# ProDoc_Board1_2_2024-09-12_1.net
KiCad netlist of a schematic drawn in EasyEDA Pro
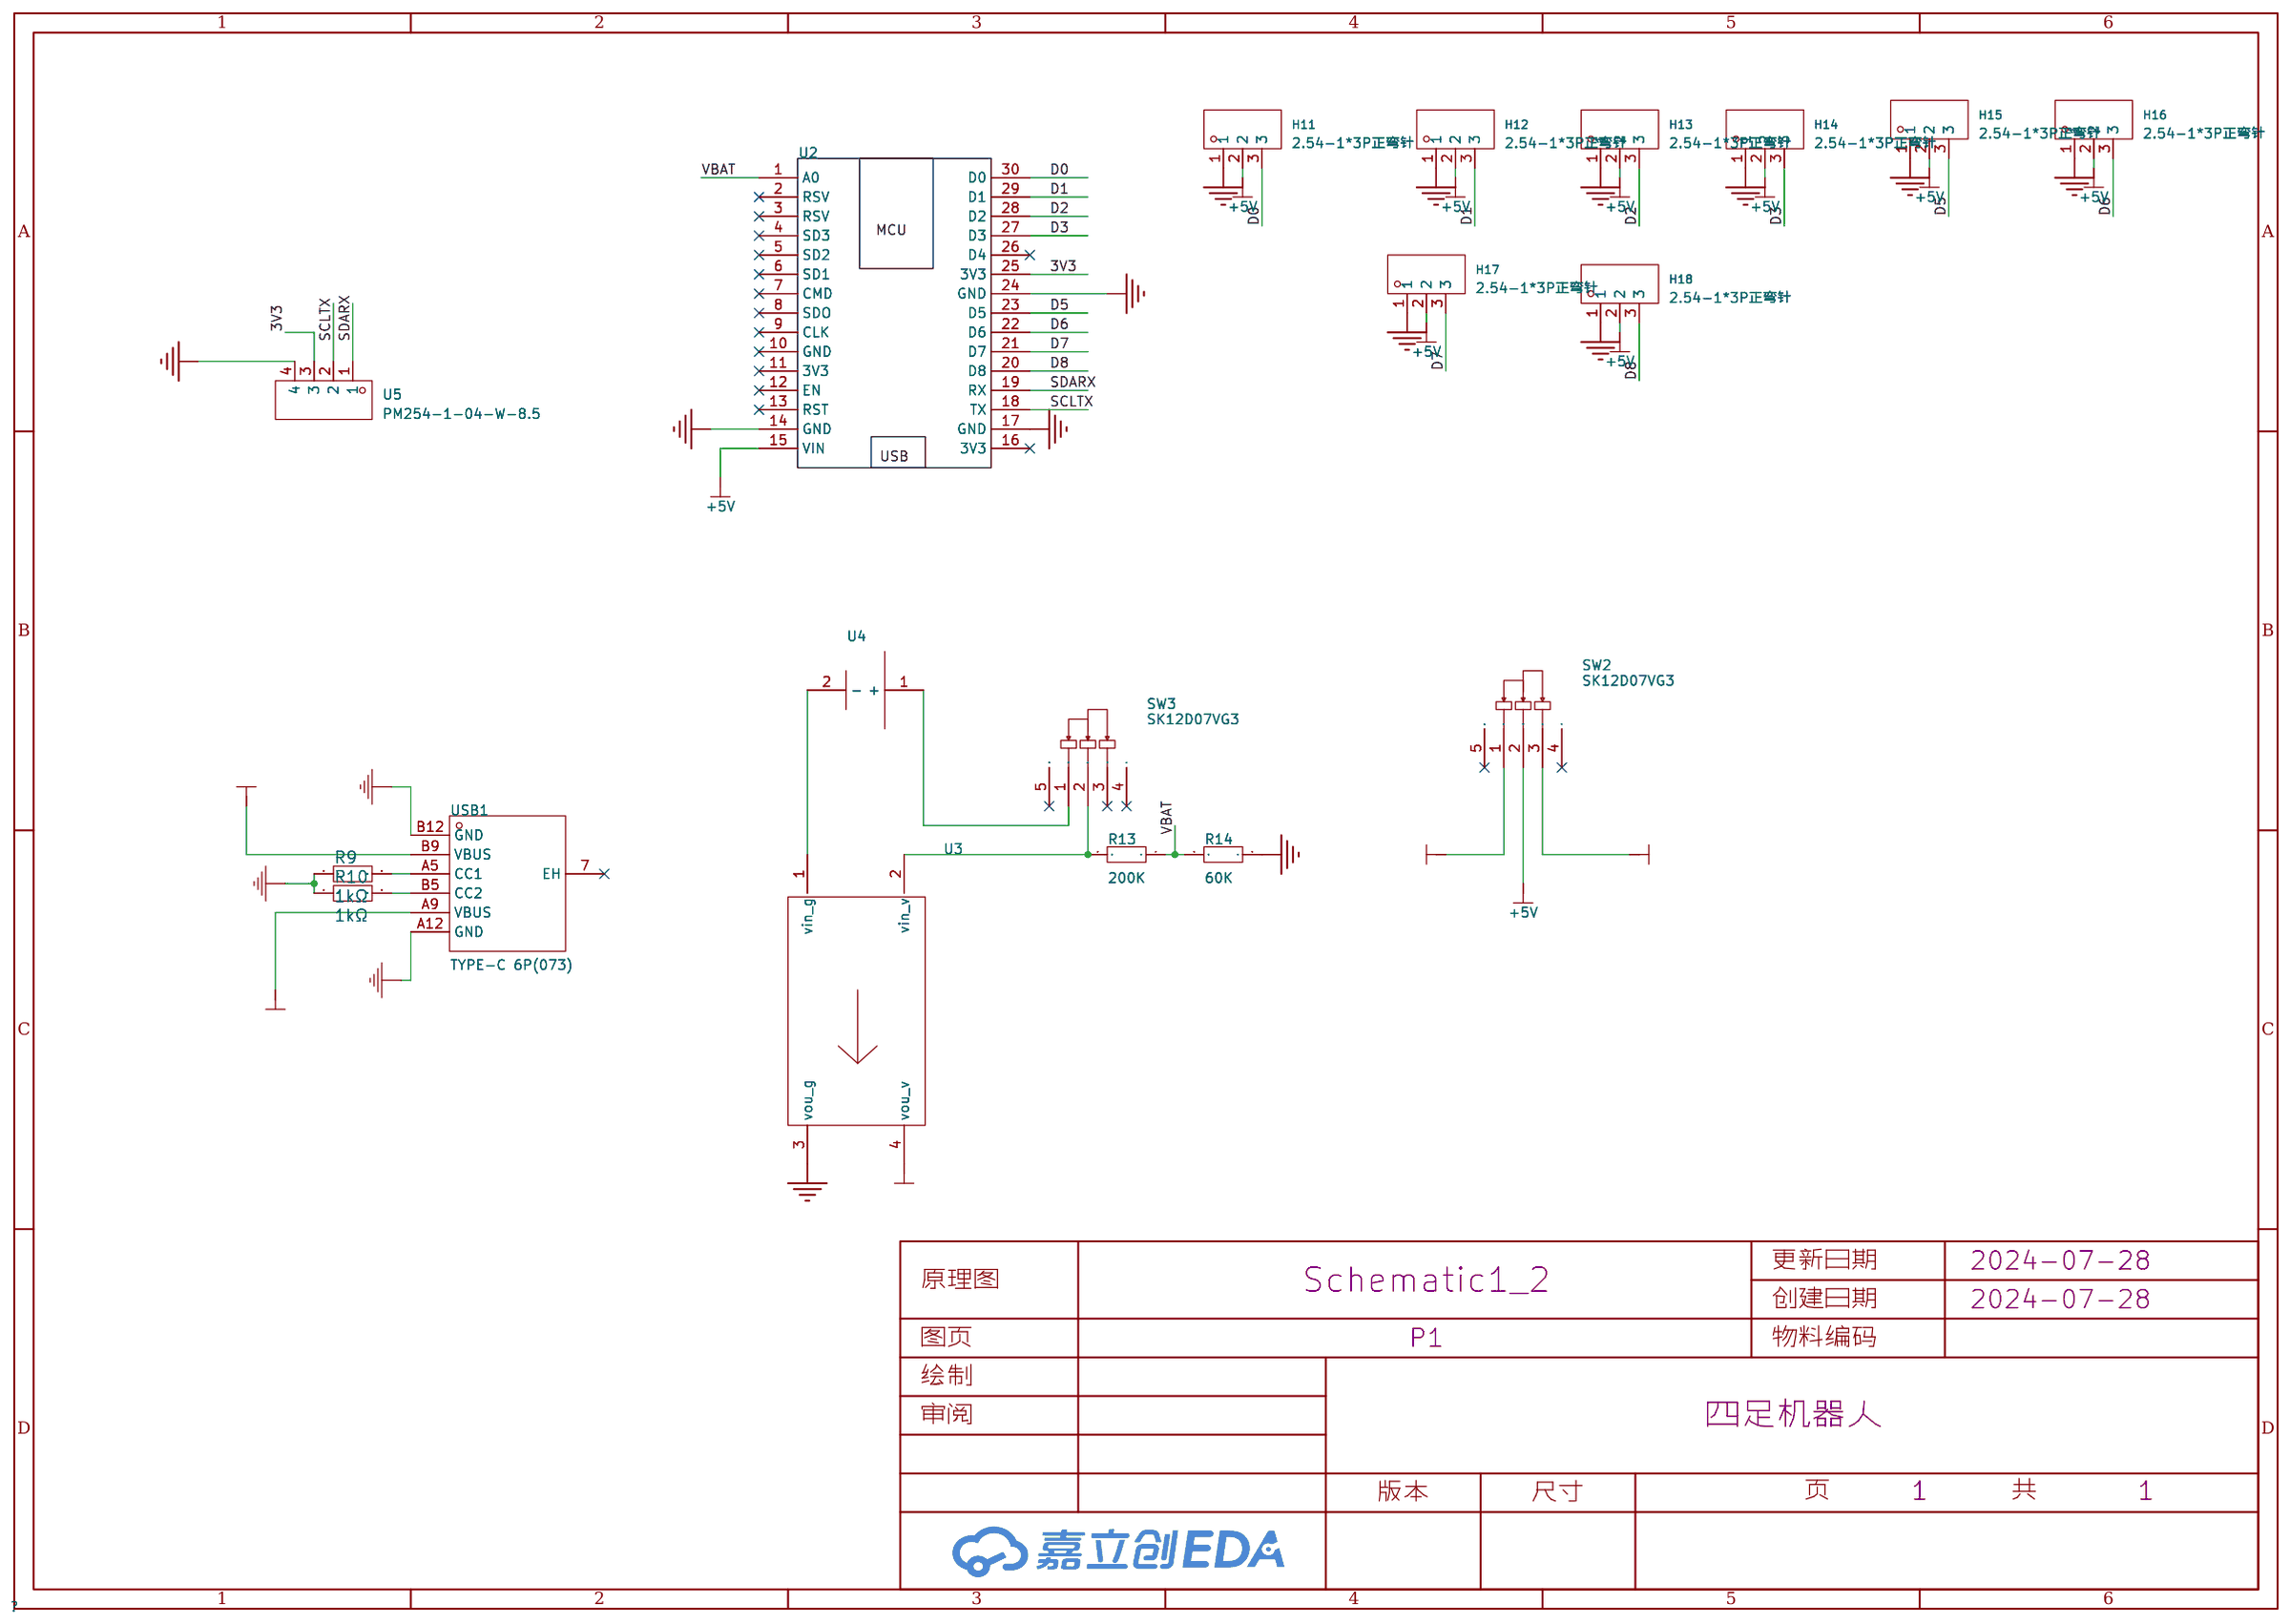
[diagram p0: schematic sheet]

(export (version "E")
  (design (tool "Eeschema 10.0.6"))
  (components
    (comp (ref "H11")
      (value "2.54-1*3P正弯针")
      (footprint "easyedapro:HDR-TH_3P-P2.54-H-M-BW7.2-P")
      (fields (field (name "Manufacturer") "BOOMELE(博穆精密)"))
      (libsource (lib "easyedapro") (part "C92159"))
    )
    (comp (ref "H12")
      (value "2.54-1*3P正弯针")
      (footprint "easyedapro:HDR-TH_3P-P2.54-H-M-BW7.2-P")
      (fields (field (name "Manufacturer") "BOOMELE(博穆精密)"))
      (libsource (lib "easyedapro") (part "C92159"))
    )
    (comp (ref "H13")
      (value "2.54-1*3P正弯针")
      (footprint "easyedapro:HDR-TH_3P-P2.54-H-M-BW7.2-P")
      (fields (field (name "Manufacturer") "BOOMELE(博穆精密)"))
      (libsource (lib "easyedapro") (part "C92159"))
    )
    (comp (ref "H14")
      (value "2.54-1*3P正弯针")
      (footprint "easyedapro:HDR-TH_3P-P2.54-H-M-BW7.2-P")
      (fields (field (name "Manufacturer") "BOOMELE(博穆精密)"))
      (libsource (lib "easyedapro") (part "C92159"))
    )
    (comp (ref "H15")
      (value "2.54-1*3P正弯针")
      (footprint "easyedapro:HDR-TH_3P-P2.54-H-M-BW7.2-P")
      (fields (field (name "Manufacturer") "BOOMELE(博穆精密)"))
      (libsource (lib "easyedapro") (part "C92159"))
    )
    (comp (ref "H16")
      (value "2.54-1*3P正弯针")
      (footprint "easyedapro:HDR-TH_3P-P2.54-H-M-BW7.2-P")
      (fields (field (name "Manufacturer") "BOOMELE(博穆精密)"))
      (libsource (lib "easyedapro") (part "C92159"))
    )
    (comp (ref "H17")
      (value "2.54-1*3P正弯针")
      (footprint "easyedapro:HDR-TH_3P-P2.54-H-M-BW7.2-P")
      (fields (field (name "Manufacturer") "BOOMELE(博穆精密)"))
      (libsource (lib "easyedapro") (part "C92159"))
    )
    (comp (ref "H18")
      (value "2.54-1*3P正弯针")
      (footprint "easyedapro:HDR-TH_3P-P2.54-H-M-BW7.2-P")
      (fields (field (name "Manufacturer") "BOOMELE(博穆精密)"))
      (libsource (lib "easyedapro") (part "C92159"))
    )
    (comp (ref "R9") (value "1kΩ") (libsource (lib "easyedapro") (part "1.5k")))
    (comp (ref "R10") (value "1kΩ") (libsource (lib "easyedapro") (part "1.5k")))
    (comp (ref "R13")
      (value "200K")
      (fields
        (field (name "Manufacturer Part") "0603WAF1002T5E")
        (field (name "Manufacturer") "UNI-ROYAL(厚声)")
      )
      (libsource (lib "easyedapro") (part "电阻"))
    )
    (comp (ref "R14")
      (value "60K")
      (fields
        (field (name "Manufacturer Part") "0603WAF1002T5E")
        (field (name "Manufacturer") "UNI-ROYAL(厚声)")
      )
      (libsource (lib "easyedapro") (part "电阻"))
    )
    (comp (ref "SW2")
      (value "SK12D07VG3")
      (footprint "easyedapro:SW-TH_SK12D07VG3")
      (description "电路结构:单刀双掷;安装方式:侧插;开关颜色:-;额定电流(DC):500mA;额定电压(DC):50V;额定电流(AC):-;额定电压(AC):-;机械寿命:5千次;")
      (fields (field (name "Manufacturer") "SHOU HAN(首韩)"))
      (libsource (lib "easyedapro") (part "SK12D07VG3_C431547"))
    )
    (comp (ref "SW3")
      (value "SK12D07VG3")
      (footprint "easyedapro:SW-TH_SK12D07VG3")
      (description "电路结构:单刀双掷;安装方式:侧插;开关颜色:-;额定电流(DC):500mA;额定电压(DC):50V;额定电流(AC):-;额定电压(AC):-;机械寿命:5千次;")
      (fields (field (name "Manufacturer") "SHOU HAN(首韩)"))
      (libsource (lib "easyedapro") (part "SK12D07VG3_C431547"))
    )
    (comp (ref "U2") (value "~") (libsource (lib "easyedapro") (part "nodemcu")))
    (comp (ref "U3") (value "~") (libsource (lib "easyedapro") (part "5v5a降压模块")))
    (comp (ref "U4") (value "~") (libsource (lib "easyedapro") (part "7.4电池输入口")))
    (comp (ref "U5")
      (value "PM254-1-04-W-8.5")
      (footprint "easyedapro:HDR-TH_4P-P2.54-H-F-W10.0-N")
      (fields (field (name "Manufacturer") "HCTL(华灿天禄)"))
      (libsource (lib "easyedapro") (part "PM254-1-04-W-8.5"))
    )
    (comp (ref "USB1")
      (value "TYPE-C 6P(073)")
      (footprint "easyedapro:TYPE-C-SMD_TYPE-C-6P")
      (description "连接器类型:Type-C;标准:-;公母:母;端口数量:1;触点数量:6P;安装方式:卧贴;额定电流 - 电源:5A;工作温度范围:-25°C~+85°C;")
      (fields (field (name "Manufacturer") "SHOU HAN(首韩)"))
      (libsource (lib "easyedapro") (part "TYPE-C 6P(073)"))
    )
  )
  (nets
    (net (code "1") (name "+5V") (class "Default")
      (node (ref "H11") (pin "2") (pinfunction "2_2") (pintype "input"))
      (node (ref "H12") (pin "2") (pinfunction "2_2") (pintype "input"))
      (node (ref "H13") (pin "2") (pinfunction "2_2") (pintype "input"))
      (node (ref "H14") (pin "2") (pinfunction "2_2") (pintype "input"))
      (node (ref "H15") (pin "2") (pinfunction "2_2") (pintype "input"))
      (node (ref "H16") (pin "2") (pinfunction "2_2") (pintype "input"))
      (node (ref "H17") (pin "2") (pinfunction "2_2") (pintype "input"))
      (node (ref "H18") (pin "2") (pinfunction "2_2") (pintype "input"))
      (node (ref "SW2") (pin "2") (pinfunction "2_2") (pintype "unspecified"))
      (node (ref "U2") (pin "15") (pinfunction "VIN_15") (pintype "input"))
    )
    (net (code "2") (name "/3V3") (class "Default")
      (node (ref "U2") (pin "25") (pinfunction "3V3_25") (pintype "input"))
      (node (ref "U5") (pin "3") (pinfunction "3_3") (pintype "unspecified"))
    )
    (net (code "3") (name "/D0") (class "Default")
      (node (ref "H11") (pin "3") (pinfunction "3_3") (pintype "input"))
      (node (ref "U2") (pin "30") (pinfunction "D0_30") (pintype "input"))
    )
    (net (code "4") (name "/D1") (class "Default")
      (node (ref "H12") (pin "3") (pinfunction "3_3") (pintype "input"))
      (node (ref "U2") (pin "29") (pinfunction "D1_29") (pintype "input"))
    )
    (net (code "5") (name "/D2") (class "Default")
      (node (ref "H13") (pin "3") (pinfunction "3_3") (pintype "input"))
      (node (ref "U2") (pin "28") (pinfunction "D2_28") (pintype "input"))
    )
    (net (code "6") (name "/D3") (class "Default")
      (node (ref "H14") (pin "3") (pinfunction "3_3") (pintype "input"))
      (node (ref "U2") (pin "27") (pinfunction "D3_27") (pintype "input"))
    )
    (net (code "7") (name "/D5") (class "Default")
      (node (ref "H15") (pin "3") (pinfunction "3_3") (pintype "input"))
      (node (ref "U2") (pin "23") (pinfunction "D5_23") (pintype "input"))
    )
    (net (code "8") (name "/D6") (class "Default")
      (node (ref "H16") (pin "3") (pinfunction "3_3") (pintype "input"))
      (node (ref "U2") (pin "22") (pinfunction "D6_22") (pintype "input"))
    )
    (net (code "9") (name "/D7") (class "Default")
      (node (ref "H17") (pin "3") (pinfunction "3_3") (pintype "input"))
      (node (ref "U2") (pin "21") (pinfunction "D7_21") (pintype "input"))
    )
    (net (code "10") (name "/D8") (class "Default")
      (node (ref "H18") (pin "3") (pinfunction "3_3") (pintype "input"))
      (node (ref "U2") (pin "20") (pinfunction "D8_20") (pintype "input"))
    )
    (net (code "11") (name "/SCLTX") (class "Default")
      (node (ref "U2") (pin "18") (pinfunction "TX_18") (pintype "input"))
      (node (ref "U5") (pin "2") (pinfunction "2_2") (pintype "unspecified"))
    )
    (net (code "12") (name "/SDARX") (class "Default")
      (node (ref "U2") (pin "19") (pinfunction "RX_19") (pintype "input"))
      (node (ref "U5") (pin "1") (pinfunction "1_1") (pintype "unspecified"))
    )
    (net (code "13") (name "/VBAT") (class "Default")
      (node (ref "R13") (pin "1") (pinfunction "1_1") (pintype "input"))
      (node (ref "R14") (pin "2") (pinfunction "2_2") (pintype "input"))
      (node (ref "U2") (pin "1") (pinfunction "A0_1") (pintype "input"))
    )
    (net (code "14") (name "GND") (class "Default")
      (node (ref "H11") (pin "1") (pinfunction "1_1") (pintype "input"))
      (node (ref "H12") (pin "1") (pinfunction "1_1") (pintype "input"))
      (node (ref "H13") (pin "1") (pinfunction "1_1") (pintype "input"))
      (node (ref "H14") (pin "1") (pinfunction "1_1") (pintype "input"))
      (node (ref "H15") (pin "1") (pinfunction "1_1") (pintype "input"))
      (node (ref "H16") (pin "1") (pinfunction "1_1") (pintype "input"))
      (node (ref "H17") (pin "1") (pinfunction "1_1") (pintype "input"))
      (node (ref "H18") (pin "1") (pinfunction "1_1") (pintype "input"))
      (node (ref "R10") (pin "1") (pinfunction "1_1") (pintype "input"))
      (node (ref "R14") (pin "1") (pinfunction "1_1") (pintype "input"))
      (node (ref "R9") (pin "1") (pinfunction "1_1") (pintype "input"))
      (node (ref "U2") (pin "14") (pinfunction "GND_14") (pintype "input"))
      (node (ref "U2") (pin "17") (pinfunction "GND_17") (pintype "input"))
      (node (ref "U2") (pin "24") (pinfunction "GND_24") (pintype "input"))
      (node (ref "U3") (pin "3") (pinfunction "vou_g_3") (pintype "input"))
      (node (ref "U5") (pin "4") (pinfunction "4_4") (pintype "unspecified"))
      (node (ref "USB1") (pin "A12") (pinfunction "GND_A12") (pintype "unspecified"))
      (node (ref "USB1") (pin "B12") (pinfunction "GND_B12") (pintype "unspecified"))
    )
    (net (code "15") (name "Net-(U3-vin_g)") (class "Default")
      (node (ref "U3") (pin "1") (pinfunction "vin_g_1") (pintype "input"))
      (node (ref "U4") (pin "2") (pinfunction "-_2") (pintype "input"))
    )
    (net (code "16") (name "Net-(U3-vin_v)") (class "Default")
      (node (ref "R13") (pin "2") (pinfunction "2_2") (pintype "input"))
      (node (ref "SW3") (pin "2") (pinfunction "2_2") (pintype "unspecified"))
      (node (ref "U3") (pin "2") (pinfunction "vin_v_2") (pintype "input"))
    )
    (net (code "17") (name "Net-(U4-+)") (class "Default")
      (node (ref "SW3") (pin "1") (pinfunction "1_1") (pintype "unspecified"))
      (node (ref "U4") (pin "1") (pinfunction "+_1") (pintype "input"))
    )
    (net (code "18") (name "Net-(USB1-CC1)") (class "Default")
      (node (ref "R9") (pin "2") (pinfunction "2_2") (pintype "input"))
      (node (ref "USB1") (pin "A5") (pinfunction "CC1_A5") (pintype "unspecified"))
    )
    (net (code "19") (name "Net-(USB1-CC2)") (class "Default")
      (node (ref "R10") (pin "2") (pinfunction "2_2") (pintype "input"))
      (node (ref "USB1") (pin "B5") (pinfunction "CC2_B5") (pintype "unspecified"))
    )
    (net (code "20") (name "USB5V") (class "Default")
      (node (ref "SW2") (pin "1") (pinfunction "1_1") (pintype "unspecified"))
      (node (ref "USB1") (pin "A9") (pinfunction "VBUS_A9") (pintype "unspecified"))
      (node (ref "USB1") (pin "B9") (pinfunction "VBUS_B9") (pintype "unspecified"))
    )
    (net (code "21") (name "VBUCK5V") (class "Default")
      (node (ref "SW2") (pin "3") (pinfunction "3_3") (pintype "unspecified"))
      (node (ref "U3") (pin "4") (pinfunction "vou_v_4") (pintype "input"))
    )
    (net (code "22") (name "unconnected-(SW2-Pad4)") (class "Default")
      (node (ref "SW2") (pin "4") (pinfunction "4_4") (pintype "unspecified+no_connect"))
    )
    (net (code "23") (name "unconnected-(SW2-Pad5)") (class "Default")
      (node (ref "SW2") (pin "5") (pinfunction "5_5") (pintype "unspecified+no_connect"))
    )
    (net (code "24") (name "unconnected-(SW3-Pad3)") (class "Default")
      (node (ref "SW3") (pin "3") (pinfunction "3_3") (pintype "unspecified+no_connect"))
    )
    (net (code "25") (name "unconnected-(SW3-Pad4)") (class "Default")
      (node (ref "SW3") (pin "4") (pinfunction "4_4") (pintype "unspecified+no_connect"))
    )
    (net (code "26") (name "unconnected-(SW3-Pad5)") (class "Default")
      (node (ref "SW3") (pin "5") (pinfunction "5_5") (pintype "unspecified+no_connect"))
    )
    (net (code "27") (name "unconnected-(U2-3V3-Pad11)") (class "Default")
      (node (ref "U2") (pin "11") (pinfunction "3V3_11") (pintype "input+no_connect"))
    )
    (net (code "28") (name "unconnected-(U2-3V3-Pad16)") (class "Default")
      (node (ref "U2") (pin "16") (pinfunction "3V3_16") (pintype "input+no_connect"))
    )
    (net (code "29") (name "unconnected-(U2-CLK-Pad9)") (class "Default")
      (node (ref "U2") (pin "9") (pinfunction "CLK_9") (pintype "input+no_connect"))
    )
    (net (code "30") (name "unconnected-(U2-CMD-Pad7)") (class "Default")
      (node (ref "U2") (pin "7") (pinfunction "CMD_7") (pintype "input+no_connect"))
    )
    (net (code "31") (name "unconnected-(U2-D4-Pad26)") (class "Default")
      (node (ref "U2") (pin "26") (pinfunction "D4_26") (pintype "input+no_connect"))
    )
    (net (code "32") (name "unconnected-(U2-EN-Pad12)") (class "Default")
      (node (ref "U2") (pin "12") (pinfunction "EN_12") (pintype "input+no_connect"))
    )
    (net (code "33") (name "unconnected-(U2-GND-Pad10)") (class "Default")
      (node (ref "U2") (pin "10") (pinfunction "GND_10") (pintype "input+no_connect"))
    )
    (net (code "34") (name "unconnected-(U2-RST-Pad13)") (class "Default")
      (node (ref "U2") (pin "13") (pinfunction "RST_13") (pintype "input+no_connect"))
    )
    (net (code "35") (name "unconnected-(U2-RSV-Pad2)") (class "Default")
      (node (ref "U2") (pin "2") (pinfunction "RSV_2") (pintype "input+no_connect"))
    )
    (net (code "36") (name "unconnected-(U2-RSV-Pad3)") (class "Default")
      (node (ref "U2") (pin "3") (pinfunction "RSV_3") (pintype "input+no_connect"))
    )
    (net (code "37") (name "unconnected-(U2-SD1-Pad6)") (class "Default")
      (node (ref "U2") (pin "6") (pinfunction "SD1_6") (pintype "input+no_connect"))
    )
    (net (code "38") (name "unconnected-(U2-SD2-Pad5)") (class "Default")
      (node (ref "U2") (pin "5") (pinfunction "SD2_5") (pintype "input+no_connect"))
    )
    (net (code "39") (name "unconnected-(U2-SD3-Pad4)") (class "Default")
      (node (ref "U2") (pin "4") (pinfunction "SD3_4") (pintype "input+no_connect"))
    )
    (net (code "40") (name "unconnected-(U2-SDO-Pad8)") (class "Default")
      (node (ref "U2") (pin "8") (pinfunction "SDO_8") (pintype "input+no_connect"))
    )
    (net (code "41") (name "unconnected-(USB1-EH-Pad7)") (class "Default")
      (node (ref "USB1") (pin "7") (pinfunction "EH_7") (pintype "unspecified+no_connect"))
    )
  )
)
